# Sheet1.net
KiCad netlist of a schematic drawn in Altium Designer
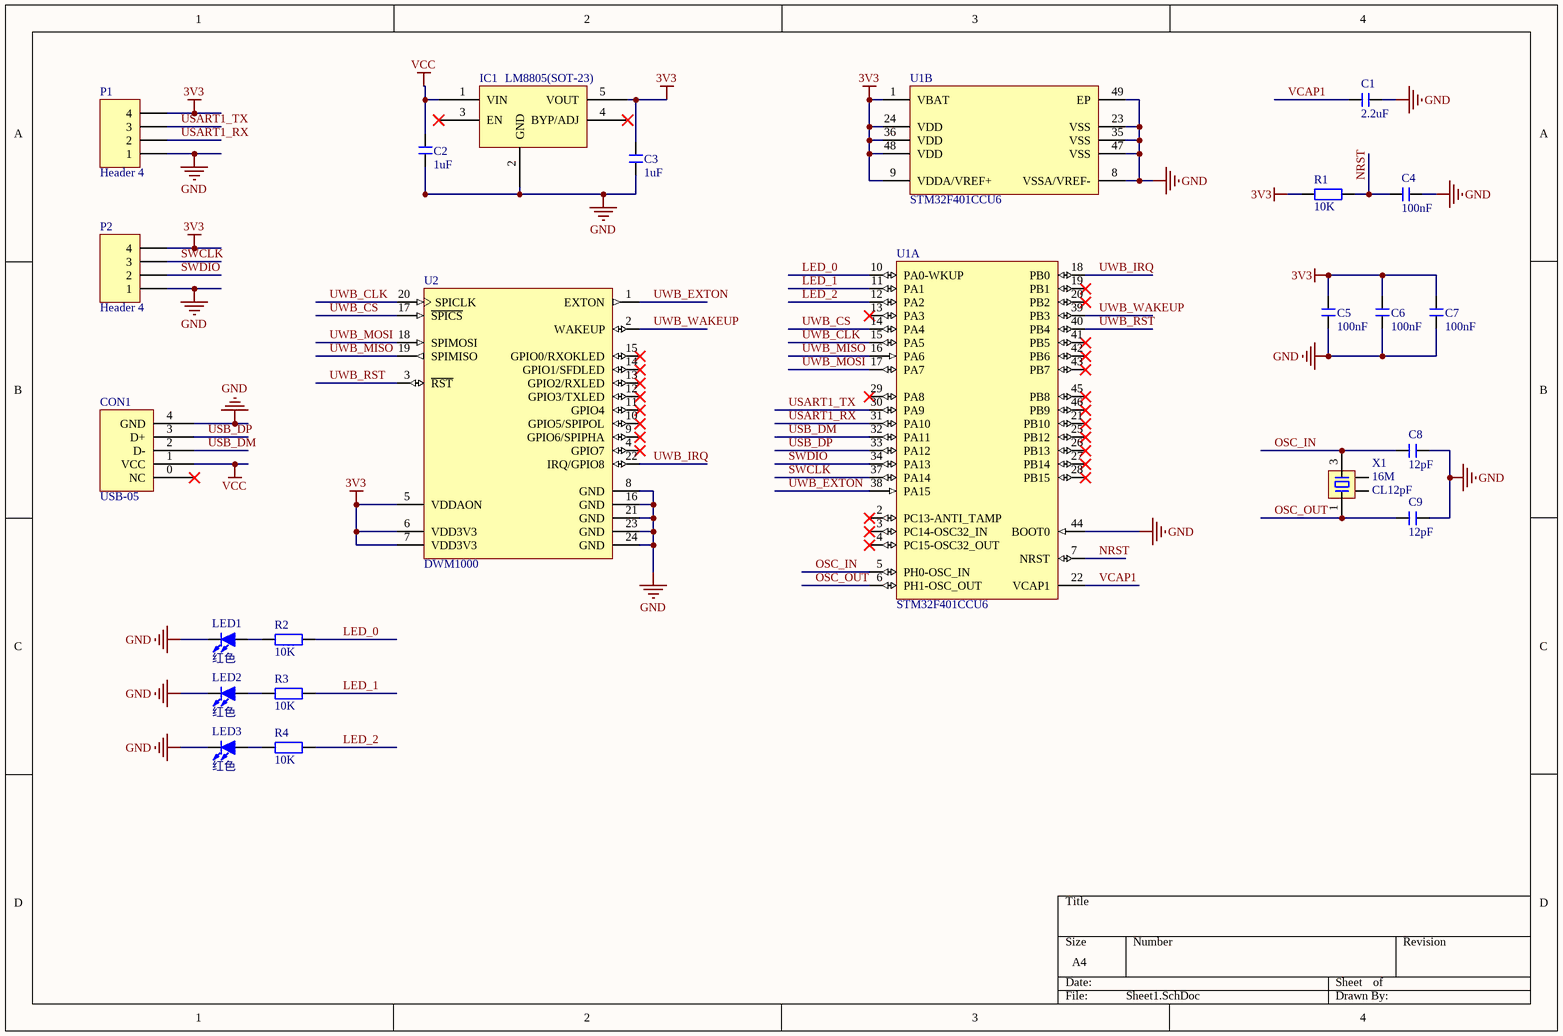
[diagram p0: Sheet1.SchDoc]

(export (version "E")
  (design (tool "Eeschema 10.0.6"))
  (components
    (comp (ref "C1")
      (value "2.2uF")
      (footprint "C 0603_L")
      (description "无极性贴片电容")
      (fields (field (name "版权归属") "源创客"))
      (libsource (lib "3.1   - 电阻-电容-电感") (part "C"))
    )
    (comp (ref "C2")
      (value "1uF")
      (footprint "C 0603_L")
      (description "无极性贴片电容")
      (fields (field (name "版权归属") "源创客"))
      (libsource (lib "3.1   - 电阻-电容-电感") (part "C"))
    )
    (comp (ref "C3")
      (value "1uF")
      (footprint "C 0603_L")
      (description "无极性贴片电容")
      (fields (field (name "版权归属") "源创客"))
      (libsource (lib "3.1   - 电阻-电容-电感") (part "C"))
    )
    (comp (ref "C4")
      (value "100nF")
      (footprint "C 0603_L")
      (description "无极性贴片电容")
      (fields (field (name "版权归属") "源创客"))
      (libsource (lib "3.1   - 电阻-电容-电感") (part "C"))
    )
    (comp (ref "C5")
      (value "100nF")
      (footprint "C 0603_L")
      (description "无极性贴片电容")
      (fields (field (name "版权归属") "源创客"))
      (libsource (lib "3.1   - 电阻-电容-电感") (part "C"))
    )
    (comp (ref "C6")
      (value "100nF")
      (footprint "C 0603_L")
      (description "无极性贴片电容")
      (fields (field (name "版权归属") "源创客"))
      (libsource (lib "3.1   - 电阻-电容-电感") (part "C"))
    )
    (comp (ref "C7")
      (value "100nF")
      (footprint "C 0603_L")
      (description "无极性贴片电容")
      (fields (field (name "版权归属") "源创客"))
      (libsource (lib "3.1   - 电阻-电容-电感") (part "C"))
    )
    (comp (ref "C8")
      (value "12pF")
      (footprint "C 0603_L")
      (description "无极性贴片电容")
      (fields (field (name "版权归属") "源创客"))
      (libsource (lib "3.1   - 电阻-电容-电感") (part "C"))
    )
    (comp (ref "C9")
      (value "12pF")
      (footprint "C 0603_L")
      (description "无极性贴片电容")
      (fields (field (name "版权归属") "源创客"))
      (libsource (lib "3.1   - 电阻-电容-电感") (part "C"))
    )
    (comp (ref "CON1") (value "USB-05") (footprint "USB-05") (libsource (lib "Schlib") (part "USB-05")))
    (comp (ref "IC1")
      (value "LM8805(SOT-23)")
      (footprint "SOT23-5N")
      (description "600mA CMOS L.D.O. Regulator")
      (libsource (lib "1.3   - 电源类芯片") (part "LM8805(SOT-23)"))
    )
    (comp (ref "LED1")
      (value "红色")
      (footprint "LED 0603G")
      (description "贴片LED")
      (fields (field (name "版权归属") "源创客"))
      (libsource (lib "9.1   - LED") (part "LED-SMD"))
    )
    (comp (ref "LED2")
      (value "红色")
      (footprint "LED 0603G")
      (description "贴片LED")
      (fields (field (name "版权归属") "源创客"))
      (libsource (lib "9.1   - LED") (part "LED-SMD"))
    )
    (comp (ref "LED3")
      (value "红色")
      (footprint "LED 0603G")
      (description "贴片LED")
      (fields (field (name "版权归属") "源创客"))
      (libsource (lib "9.1   - LED") (part "LED-SMD"))
    )
    (comp (ref "P1")
      (value "Header 4")
      (footprint "MX 1.25-WS-4P")
      (description "Header, 4-Pin")
      (fields (field (name "PUBLISHER") "Altium Limited"))
      (libsource (lib "Miscellaneous Connectors") (part "Header 4"))
    )
    (comp (ref "P2")
      (value "Header 4")
      (footprint "MX 1.25-WS-4P")
      (description "Header, 4-Pin")
      (fields (field (name "PUBLISHER") "Altium Limited"))
      (libsource (lib "Miscellaneous Connectors") (part "Header 4"))
    )
    (comp (ref "R1")
      (value "10K")
      (footprint "R 0603_L")
      (description "贴片电阻")
      (fields (field (name "版权归属") "源创客"))
      (libsource (lib "3.1   - 电阻-电容-电感") (part "R"))
    )
    (comp (ref "R2")
      (value "10K")
      (footprint "R 0603_L")
      (description "贴片电阻")
      (fields (field (name "版权归属") "源创客"))
      (libsource (lib "3.1   - 电阻-电容-电感") (part "R"))
    )
    (comp (ref "R3")
      (value "10K")
      (footprint "R 0603_L")
      (description "贴片电阻")
      (fields (field (name "版权归属") "源创客"))
      (libsource (lib "3.1   - 电阻-电容-电感") (part "R"))
    )
    (comp (ref "R4")
      (value "10K")
      (footprint "R 0603_L")
      (description "贴片电阻")
      (fields (field (name "版权归属") "源创客"))
      (libsource (lib "3.1   - 电阻-电容-电感") (part "R"))
    )
    (comp (ref "U1")
      (value "STM32F401CCU6")
      (footprint "STM-UFQFPN48_N")
      (fields (field (name "MANUFACTURER") "STMicroelectronics"))
      (libsource (lib "Altium Content Vault") (part "MC-ARM-STM32F401-SQ48"))
    )
    (comp (ref "U2")
      (value "DWM1000")
      (footprint "DECW-DWM1000-24_V")
      (description "DW M1000 IEEE 802.15.4 -2011 UWB Transceiver Module")
      (fields (field (name "MANUFACTURER") "Decawave"))
      (libsource (lib "Altium Content Vault") (part "DECW-DWM1000-24"))
    )
    (comp (ref "X1")
      (value "16M")
      (footprint "OSC 3225-4P")
      (description "4脚无源晶振")
      (fields (field (name "负载电容") "CL12pF") (field (name "版权归属") "源创客"))
      (libsource (lib "10.1 - 保险丝-晶振") (part "XTAL-4P"))
    )
  )
  (nets
    (net (code "1") (name "/LED_0") (class "Default")
      (node (ref "R2") (pin "2") (pinfunction "2_2") (pintype "passive"))
      (node (ref "U1") (pin "10") (pinfunction "PA0-WKUP_10") (pintype "bidirectional"))
    )
    (net (code "2") (name "/LED_1") (class "Default")
      (node (ref "R3") (pin "2") (pinfunction "2_2") (pintype "passive"))
      (node (ref "U1") (pin "11") (pinfunction "PA1_11") (pintype "bidirectional"))
    )
    (net (code "3") (name "/LED_2") (class "Default")
      (node (ref "R4") (pin "2") (pinfunction "2_2") (pintype "passive"))
      (node (ref "U1") (pin "12") (pinfunction "PA2_12") (pintype "bidirectional"))
    )
    (net (code "4") (name "/NRST") (class "Default")
      (node (ref "C4") (pin "2") (pinfunction "2_2") (pintype "passive"))
      (node (ref "R1") (pin "2") (pinfunction "2_2") (pintype "passive"))
      (node (ref "U1") (pin "7") (pinfunction "NRST_7") (pintype "bidirectional"))
    )
    (net (code "5") (name "/OSC_IN") (class "Default")
      (node (ref "C8") (pin "1") (pinfunction "1_1") (pintype "passive"))
      (node (ref "U1") (pin "5") (pinfunction "PH0-OSC_IN_5") (pintype "bidirectional"))
      (node (ref "X1") (pin "3") (pinfunction "3_3") (pintype "passive"))
    )
    (net (code "6") (name "/OSC_OUT") (class "Default")
      (node (ref "C9") (pin "1") (pinfunction "1_1") (pintype "passive"))
      (node (ref "U1") (pin "6") (pinfunction "PH1-OSC_OUT_6") (pintype "bidirectional"))
      (node (ref "X1") (pin "1") (pinfunction "1_1") (pintype "passive"))
    )
    (net (code "7") (name "/SWCLK") (class "Default")
      (node (ref "P2") (pin "3") (pinfunction "3_3") (pintype "passive"))
      (node (ref "U1") (pin "37") (pinfunction "PA14_37") (pintype "bidirectional"))
    )
    (net (code "8") (name "/SWDIO") (class "Default")
      (node (ref "P2") (pin "2") (pinfunction "2_2") (pintype "passive"))
      (node (ref "U1") (pin "34") (pinfunction "PA13_34") (pintype "bidirectional"))
    )
    (net (code "9") (name "/USART1_RX") (class "Default")
      (node (ref "P1") (pin "2") (pinfunction "2_2") (pintype "passive"))
      (node (ref "U1") (pin "31") (pinfunction "PA10_31") (pintype "bidirectional"))
    )
    (net (code "10") (name "/USART1_TX") (class "Default")
      (node (ref "P1") (pin "3") (pinfunction "3_3") (pintype "passive"))
      (node (ref "U1") (pin "30") (pinfunction "PA9_30") (pintype "bidirectional"))
    )
    (net (code "11") (name "/USB_DM") (class "Default")
      (node (ref "CON1") (pin "2") (pinfunction "D-_2") (pintype "passive"))
      (node (ref "U1") (pin "32") (pinfunction "PA11_32") (pintype "bidirectional"))
    )
    (net (code "12") (name "/USB_DP") (class "Default")
      (node (ref "CON1") (pin "3") (pinfunction "D+_3") (pintype "passive"))
      (node (ref "U1") (pin "33") (pinfunction "PA12_33") (pintype "bidirectional"))
    )
    (net (code "13") (name "/UWB_CLK") (class "Default")
      (node (ref "U1") (pin "15") (pinfunction "PA5_15") (pintype "bidirectional"))
      (node (ref "U2") (pin "20") (pinfunction "SPICLK_20") (pintype "input"))
    )
    (net (code "14") (name "/UWB_CS") (class "Default")
      (node (ref "U1") (pin "14") (pinfunction "PA4_14") (pintype "bidirectional"))
      (node (ref "U2") (pin "17") (pinfunction "~{SPICS}_17") (pintype "input"))
    )
    (net (code "15") (name "/UWB_EXTON") (class "Default")
      (node (ref "U1") (pin "38") (pinfunction "PA15_38") (pintype "input"))
      (node (ref "U2") (pin "1") (pinfunction "EXTON_1") (pintype "output"))
    )
    (net (code "16") (name "/UWB_IRQ") (class "Default")
      (node (ref "U1") (pin "18") (pinfunction "PB0_18") (pintype "bidirectional"))
      (node (ref "U2") (pin "22") (pinfunction "IRQ/GPIO8_22") (pintype "bidirectional"))
    )
    (net (code "17") (name "/UWB_MISO") (class "Default")
      (node (ref "U1") (pin "16") (pinfunction "PA6_16") (pintype "input"))
      (node (ref "U2") (pin "19") (pinfunction "SPIMISO_19") (pintype "output"))
    )
    (net (code "18") (name "/UWB_MOSI") (class "Default")
      (node (ref "U1") (pin "17") (pinfunction "PA7_17") (pintype "bidirectional"))
      (node (ref "U2") (pin "18") (pinfunction "SPIMOSI_18") (pintype "input"))
    )
    (net (code "19") (name "/UWB_RST") (class "Default")
      (node (ref "U1") (pin "40") (pinfunction "PB4_40") (pintype "bidirectional"))
      (node (ref "U2") (pin "3") (pinfunction "~{RST}_3") (pintype "bidirectional"))
    )
    (net (code "20") (name "/UWB_WAKEUP") (class "Default")
      (node (ref "U1") (pin "39") (pinfunction "PB3_39") (pintype "bidirectional"))
      (node (ref "U2") (pin "2") (pinfunction "WAKEUP_2") (pintype "bidirectional"))
    )
    (net (code "21") (name "/VCAP1") (class "Default")
      (node (ref "C1") (pin "1") (pinfunction "1_1") (pintype "passive"))
      (node (ref "U1") (pin "22") (pinfunction "VCAP1_22") (pintype "power_in"))
    )
    (net (code "22") (name "3V3") (class "Default")
      (node (ref "C3") (pin "2") (pinfunction "2_2") (pintype "passive"))
      (node (ref "C5") (pin "2") (pinfunction "2_2") (pintype "passive"))
      (node (ref "C6") (pin "2") (pinfunction "2_2") (pintype "passive"))
      (node (ref "C7") (pin "2") (pinfunction "2_2") (pintype "passive"))
      (node (ref "IC1") (pin "5") (pinfunction "VOUT_5") (pintype "passive"))
      (node (ref "P1") (pin "4") (pinfunction "4_4") (pintype "passive"))
      (node (ref "P2") (pin "4") (pinfunction "4_4") (pintype "passive"))
      (node (ref "R1") (pin "1") (pinfunction "1_1") (pintype "passive"))
      (node (ref "U1") (pin "1") (pinfunction "VBAT_1") (pintype "power_in"))
      (node (ref "U1") (pin "24") (pinfunction "VDD_24") (pintype "power_in"))
      (node (ref "U1") (pin "36") (pinfunction "VDD_36") (pintype "power_in"))
      (node (ref "U1") (pin "48") (pinfunction "VDD_48") (pintype "power_in"))
      (node (ref "U1") (pin "9") (pinfunction "VDDA/VREF+_9") (pintype "power_in"))
      (node (ref "U2") (pin "5") (pinfunction "VDDAON_5") (pintype "power_in"))
      (node (ref "U2") (pin "6") (pinfunction "VDD3V3_6") (pintype "power_in"))
      (node (ref "U2") (pin "7") (pinfunction "VDD3V3_7") (pintype "power_in"))
    )
    (net (code "23") (name "GND") (class "Default")
      (node (ref "C1") (pin "2") (pinfunction "2_2") (pintype "passive"))
      (node (ref "C2") (pin "1") (pinfunction "1_1") (pintype "passive"))
      (node (ref "C3") (pin "1") (pinfunction "1_1") (pintype "passive"))
      (node (ref "C4") (pin "1") (pinfunction "1_1") (pintype "passive"))
      (node (ref "C5") (pin "1") (pinfunction "1_1") (pintype "passive"))
      (node (ref "C6") (pin "1") (pinfunction "1_1") (pintype "passive"))
      (node (ref "C7") (pin "1") (pinfunction "1_1") (pintype "passive"))
      (node (ref "C8") (pin "2") (pinfunction "2_2") (pintype "passive"))
      (node (ref "C9") (pin "2") (pinfunction "2_2") (pintype "passive"))
      (node (ref "CON1") (pin "4") (pinfunction "GND_4") (pintype "passive"))
      (node (ref "IC1") (pin "2") (pinfunction "GND_2") (pintype "passive"))
      (node (ref "LED1") (pin "2") (pinfunction "K_2") (pintype "passive"))
      (node (ref "LED2") (pin "2") (pinfunction "K_2") (pintype "passive"))
      (node (ref "LED3") (pin "2") (pinfunction "K_2") (pintype "passive"))
      (node (ref "P1") (pin "1") (pinfunction "1_1") (pintype "passive"))
      (node (ref "P2") (pin "1") (pinfunction "1_1") (pintype "passive"))
      (node (ref "U1") (pin "23") (pinfunction "VSS_23") (pintype "power_in"))
      (node (ref "U1") (pin "35") (pinfunction "VSS_35") (pintype "power_in"))
      (node (ref "U1") (pin "44") (pinfunction "BOOT0_44") (pintype "input"))
      (node (ref "U1") (pin "47") (pinfunction "VSS_47") (pintype "power_in"))
      (node (ref "U1") (pin "49") (pinfunction "EP_49") (pintype "power_in"))
      (node (ref "U1") (pin "8") (pinfunction "VSSA/VREF-_8") (pintype "power_in"))
      (node (ref "U2") (pin "16") (pinfunction "GND_16") (pintype "power_in"))
      (node (ref "U2") (pin "21") (pinfunction "GND_21") (pintype "power_in"))
      (node (ref "U2") (pin "23") (pinfunction "GND_23") (pintype "power_in"))
      (node (ref "U2") (pin "24") (pinfunction "GND_24") (pintype "power_in"))
      (node (ref "U2") (pin "8") (pinfunction "GND_8") (pintype "power_in"))
    )
    (net (code "24") (name "Net-(LED1-A)") (class "Default")
      (node (ref "LED1") (pin "1") (pinfunction "A_1") (pintype "passive"))
      (node (ref "R2") (pin "1") (pinfunction "1_1") (pintype "passive"))
    )
    (net (code "25") (name "Net-(LED2-A)") (class "Default")
      (node (ref "LED2") (pin "1") (pinfunction "A_1") (pintype "passive"))
      (node (ref "R3") (pin "1") (pinfunction "1_1") (pintype "passive"))
    )
    (net (code "26") (name "Net-(LED3-A)") (class "Default")
      (node (ref "LED3") (pin "1") (pinfunction "A_1") (pintype "passive"))
      (node (ref "R4") (pin "1") (pinfunction "1_1") (pintype "passive"))
    )
    (net (code "27") (name "VCC") (class "Default")
      (node (ref "C2") (pin "2") (pinfunction "2_2") (pintype "passive"))
      (node (ref "CON1") (pin "1") (pinfunction "VCC_1") (pintype "passive"))
      (node (ref "IC1") (pin "1") (pinfunction "VIN_1") (pintype "passive"))
    )
    (net (code "28") (name "unconnected-(CON1-NC-Pad0)") (class "Default")
      (node (ref "CON1") (pin "0") (pinfunction "NC_0") (pintype "passive+no_connect"))
    )
    (net (code "29") (name "unconnected-(IC1-BYP{slash}ADJ-Pad4)") (class "Default")
      (node (ref "IC1") (pin "4") (pinfunction "BYP/ADJ_4") (pintype "passive+no_connect"))
    )
    (net (code "30") (name "unconnected-(IC1-EN-Pad3)") (class "Default")
      (node (ref "IC1") (pin "3") (pinfunction "EN_3") (pintype "passive+no_connect"))
    )
    (net (code "31") (name "unconnected-(U1A-PA3-Pad13)") (class "Default")
      (node (ref "U1") (pin "13") (pinfunction "PA3_13") (pintype "bidirectional+no_connect"))
    )
    (net (code "32") (name "unconnected-(U1A-PA8-Pad29)") (class "Default")
      (node (ref "U1") (pin "29") (pinfunction "PA8_29") (pintype "bidirectional+no_connect"))
    )
    (net (code "33") (name "unconnected-(U1A-PB1-Pad19)") (class "Default")
      (node (ref "U1") (pin "19") (pinfunction "PB1_19") (pintype "bidirectional+no_connect"))
    )
    (net (code "34") (name "unconnected-(U1A-PB2-Pad20)") (class "Default")
      (node (ref "U1") (pin "20") (pinfunction "PB2_20") (pintype "bidirectional+no_connect"))
    )
    (net (code "35") (name "unconnected-(U1A-PB5-Pad41)") (class "Default")
      (node (ref "U1") (pin "41") (pinfunction "PB5_41") (pintype "bidirectional+no_connect"))
    )
    (net (code "36") (name "unconnected-(U1A-PB6-Pad42)") (class "Default")
      (node (ref "U1") (pin "42") (pinfunction "PB6_42") (pintype "bidirectional+no_connect"))
    )
    (net (code "37") (name "unconnected-(U1A-PB7-Pad43)") (class "Default")
      (node (ref "U1") (pin "43") (pinfunction "PB7_43") (pintype "bidirectional+no_connect"))
    )
    (net (code "38") (name "unconnected-(U1A-PB8-Pad45)") (class "Default")
      (node (ref "U1") (pin "45") (pinfunction "PB8_45") (pintype "bidirectional+no_connect"))
    )
    (net (code "39") (name "unconnected-(U1A-PB9-Pad46)") (class "Default")
      (node (ref "U1") (pin "46") (pinfunction "PB9_46") (pintype "bidirectional+no_connect"))
    )
    (net (code "40") (name "unconnected-(U1A-PB10-Pad21)") (class "Default")
      (node (ref "U1") (pin "21") (pinfunction "PB10_21") (pintype "bidirectional+no_connect"))
    )
    (net (code "41") (name "unconnected-(U1A-PB12-Pad25)") (class "Default")
      (node (ref "U1") (pin "25") (pinfunction "PB12_25") (pintype "bidirectional+no_connect"))
    )
    (net (code "42") (name "unconnected-(U1A-PB13-Pad26)") (class "Default")
      (node (ref "U1") (pin "26") (pinfunction "PB13_26") (pintype "bidirectional+no_connect"))
    )
    (net (code "43") (name "unconnected-(U1A-PB14-Pad27)") (class "Default")
      (node (ref "U1") (pin "27") (pinfunction "PB14_27") (pintype "bidirectional+no_connect"))
    )
    (net (code "44") (name "unconnected-(U1A-PB15-Pad28)") (class "Default")
      (node (ref "U1") (pin "28") (pinfunction "PB15_28") (pintype "bidirectional+no_connect"))
    )
    (net (code "45") (name "unconnected-(U1A-PC13-ANTI_TAMP-Pad2)") (class "Default")
      (node (ref "U1") (pin "2") (pinfunction "PC13-ANTI_TAMP_2") (pintype "bidirectional+no_connect"))
    )
    (net (code "46") (name "unconnected-(U1A-PC14-OSC32_IN-Pad3)") (class "Default")
      (node (ref "U1") (pin "3") (pinfunction "PC14-OSC32_IN_3") (pintype "bidirectional+no_connect"))
    )
    (net (code "47") (name "unconnected-(U1A-PC15-OSC32_OUT-Pad4)") (class "Default")
      (node (ref "U1") (pin "4") (pinfunction "PC15-OSC32_OUT_4") (pintype "bidirectional+no_connect"))
    )
    (net (code "48") (name "unconnected-(U2-GPIO0{slash}RXOKLED-Pad15)") (class "Default")
      (node (ref "U2") (pin "15") (pinfunction "GPIO0/RXOKLED_15") (pintype "bidirectional+no_connect"))
    )
    (net (code "49") (name "unconnected-(U2-GPIO1{slash}SFDLED-Pad14)") (class "Default")
      (node (ref "U2") (pin "14") (pinfunction "GPIO1/SFDLED_14") (pintype "bidirectional+no_connect"))
    )
    (net (code "50") (name "unconnected-(U2-GPIO2{slash}RXLED-Pad13)") (class "Default")
      (node (ref "U2") (pin "13") (pinfunction "GPIO2/RXLED_13") (pintype "bidirectional+no_connect"))
    )
    (net (code "51") (name "unconnected-(U2-GPIO3{slash}TXLED-Pad12)") (class "Default")
      (node (ref "U2") (pin "12") (pinfunction "GPIO3/TXLED_12") (pintype "bidirectional+no_connect"))
    )
    (net (code "52") (name "unconnected-(U2-GPIO4-Pad11)") (class "Default")
      (node (ref "U2") (pin "11") (pinfunction "GPIO4_11") (pintype "bidirectional+no_connect"))
    )
    (net (code "53") (name "unconnected-(U2-GPIO5{slash}SPIPOL-Pad10)") (class "Default")
      (node (ref "U2") (pin "10") (pinfunction "GPIO5/SPIPOL_10") (pintype "bidirectional+no_connect"))
    )
    (net (code "54") (name "unconnected-(U2-GPIO6{slash}SPIPHA-Pad9)") (class "Default")
      (node (ref "U2") (pin "9") (pinfunction "GPIO6/SPIPHA_9") (pintype "bidirectional+no_connect"))
    )
    (net (code "55") (name "unconnected-(U2-GPIO7-Pad4)") (class "Default")
      (node (ref "U2") (pin "4") (pinfunction "GPIO7_4") (pintype "bidirectional+no_connect"))
    )
    (net (code "56") (name "unconnected-(X1-Pad2)") (class "Default")
      (node (ref "X1") (pin "2") (pinfunction "2_2") (pintype "passive"))
    )
    (net (code "57") (name "unconnected-(X1-Pad4)") (class "Default")
      (node (ref "X1") (pin "4") (pinfunction "4_4") (pintype "passive"))
    )
  )
)
